# Schematic_EasyEDA_-_openELECTRO_-_ARDUIN.net
KiCad netlist of a schematic drawn in EasyEDA
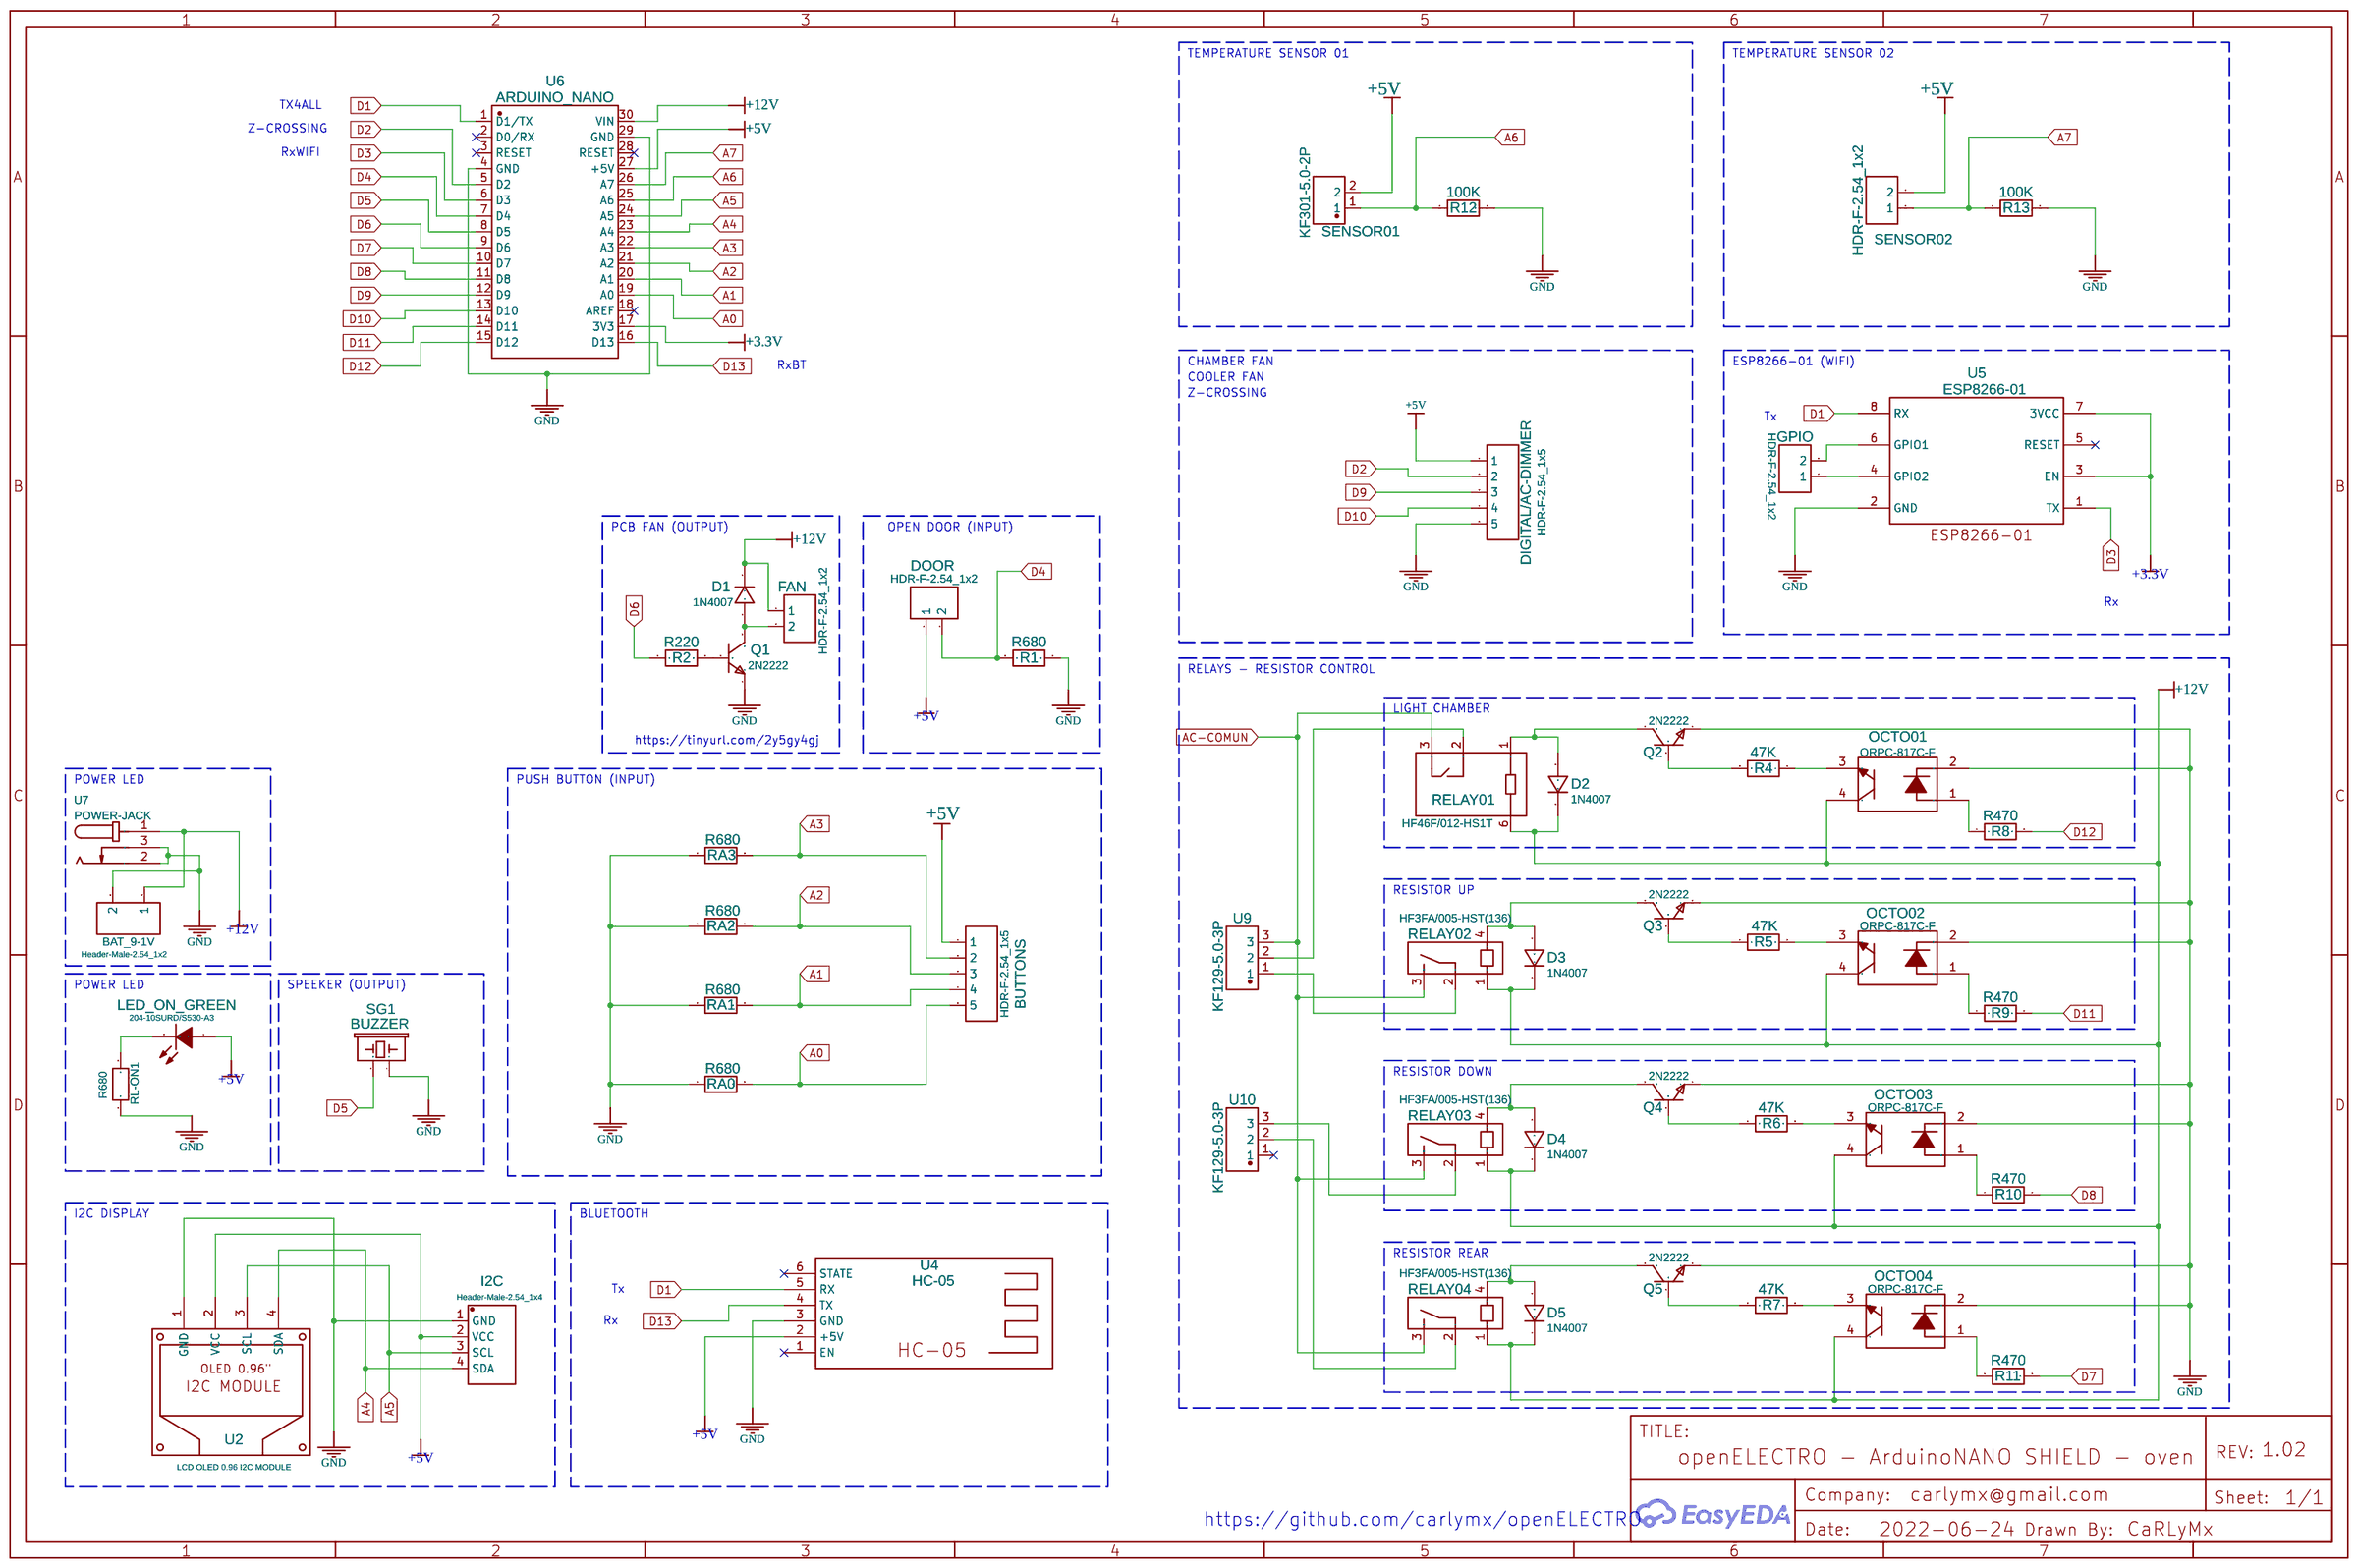
[diagram p0: schematic sheet]

(export (version "E")
  (design (tool "Eeschema 10.0.6"))
  (components
    (comp (ref "BAT_9-1V")
      (value "Header-Male-2.54_1x2")
      (fields (field (name "BOM_Manufacturer Part") "826629-2") (field (name "BOM_Supplier Part") "C86471"))
      (libsource (lib "") (part "Unknown_65_-400"))
    )
    (comp (ref "BUTTONS")
      (value "HDR-F-2.54_1x5")
      (fields (field (name "BOM_Supplier Part") "C50950"))
      (libsource (lib "") (part "HDR-F-2.54_1x5"))
    )
    (comp (ref "D1")
      (value "1N4007")
      (fields (field (name "BOM_Supplier Part") "C106903"))
      (libsource (lib "") (part "1N4007_1"))
    )
    (comp (ref "D2")
      (value "1N4007")
      (fields (field (name "BOM_Supplier Part") "C106903"))
      (libsource (lib "") (part "1N4007"))
    )
    (comp (ref "D3")
      (value "1N4007")
      (fields (field (name "BOM_Supplier Part") "C106903"))
      (libsource (lib "") (part "1N4007"))
    )
    (comp (ref "D4")
      (value "1N4007")
      (fields (field (name "BOM_Supplier Part") "C106903"))
      (libsource (lib "") (part "1N4007"))
    )
    (comp (ref "D5")
      (value "1N4007")
      (fields (field (name "BOM_Supplier Part") "C106903"))
      (libsource (lib "") (part "1N4007"))
    )
    (comp (ref "DIGITAL/AC-DIMMER")
      (value "HDR-F-2.54_1x5")
      (fields (field (name "BOM_Supplier Part") "C50950"))
      (libsource (lib "") (part "HDR-F-2.54_1x5_1"))
    )
    (comp (ref "DOOR")
      (value "HDR-F-2.54_1x2")
      (fields (field (name "BOM_Supplier Part") "C49661"))
      (libsource (lib "") (part "HDR-F-2.54_1x2"))
    )
    (comp (ref "FAN")
      (value "HDR-F-2.54_1x2")
      (fields (field (name "BOM_Supplier Part") "C49661"))
      (libsource (lib "") (part "HDR-F-2.54_1x2_2"))
    )
    (comp (ref "GPIO")
      (value "HDR-F-2.54_1x2")
      (fields (field (name "BOM_Supplier Part") "C49661"))
      (libsource (lib "") (part "HDR-F-2.54_1x2_3"))
    )
    (comp (ref "I2C")
      (value "Header-Male-2.54_1x4")
      (fields
        (field (name "BOM_Manufacturer Part") "210S-1*4P L=11.6MMGold-plated black")
        (field (name "BOM_Supplier Part") "C124378")
      )
      (libsource (lib "") (part "Unknown_290_-125"))
    )
    (comp (ref "LED_ON_GREEN")
      (value "204-10SURD/S530-A3")
      (fields (field (name "BOM_Supplier Part") "C99772"))
      (libsource (lib "") (part "Unknown_100_-315"))
    )
    (comp (ref "OCTO01")
      (value "ORPC-817C-F")
      (fields (field (name "BOM_Supplier Part") "C2842770"))
      (libsource (lib "") (part "ORPC-817C-F"))
    )
    (comp (ref "OCTO02")
      (value "ORPC-817C-F")
      (fields (field (name "BOM_Supplier Part") "C2842770"))
      (libsource (lib "") (part "ORPC-817C-F"))
    )
    (comp (ref "OCTO03")
      (value "ORPC-817C-F")
      (fields (field (name "BOM_Supplier Part") "C2842770"))
      (libsource (lib "") (part "ORPC-817C-F"))
    )
    (comp (ref "OCTO04")
      (value "ORPC-817C-F")
      (fields (field (name "BOM_Supplier Part") "C2842770"))
      (libsource (lib "") (part "ORPC-817C-F"))
    )
    (comp (ref "Q1")
      (value "2N2222")
      (fields (field (name "BOM_Supplier Part") "C118536"))
      (libsource (lib "") (part "2N2222_1"))
    )
    (comp (ref "Q2")
      (value "2N2222")
      (fields (field (name "BOM_Supplier Part") "C118536"))
      (libsource (lib "") (part "2N2222"))
    )
    (comp (ref "Q3")
      (value "2N2222")
      (fields (field (name "BOM_Supplier Part") "C118536"))
      (libsource (lib "") (part "2N2222"))
    )
    (comp (ref "Q4")
      (value "2N2222")
      (fields (field (name "BOM_Supplier Part") "C118536"))
      (libsource (lib "") (part "2N2222"))
    )
    (comp (ref "Q5")
      (value "2N2222")
      (fields (field (name "BOM_Supplier Part") "C118536"))
      (libsource (lib "") (part "2N2222"))
    )
    (comp (ref "R1") (value "R680") (libsource (lib "") (part "R_0603_EU_1")))
    (comp (ref "R2") (value "R220") (libsource (lib "") (part "R_0603_EU")))
    (comp (ref "R4") (value "47K") (libsource (lib "") (part "R_0603_EU_1")))
    (comp (ref "R5") (value "47K") (libsource (lib "") (part "R_0603_EU")))
    (comp (ref "R6") (value "47K") (libsource (lib "") (part "R_0603_EU")))
    (comp (ref "R7") (value "47K") (libsource (lib "") (part "R_0603_EU")))
    (comp (ref "R8") (value "R470") (libsource (lib "") (part "R_0603_EU")))
    (comp (ref "R9") (value "R470") (libsource (lib "") (part "R_0603_EU")))
    (comp (ref "R10") (value "R470") (libsource (lib "") (part "R_0603_EU")))
    (comp (ref "R11") (value "R470") (libsource (lib "") (part "R_0603_EU")))
    (comp (ref "R12") (value "100K") (libsource (lib "") (part "R_0603_EU")))
    (comp (ref "R13") (value "100K") (libsource (lib "") (part "R_0603_EU")))
    (comp (ref "RA0") (value "R680") (libsource (lib "") (part "Res_AXIAL-0.3(1/8W)_EU")))
    (comp (ref "RA1") (value "R680") (libsource (lib "") (part "Res_AXIAL-0.3(1/8W)_EU")))
    (comp (ref "RA2") (value "R680") (libsource (lib "") (part "Res_AXIAL-0.3(1/8W)_EU")))
    (comp (ref "RA3") (value "R680") (libsource (lib "") (part "Res_AXIAL-0.3(1/8W)_EU")))
    (comp (ref "RELAY01")
      (value "HF46F/012-HS1T")
      (fields (field (name "BOM_Supplier Part") "C2976852"))
      (libsource (lib "") (part "HF46F/012-HS1T"))
    )
    (comp (ref "RELAY02")
      (value "HF3FA/005-HST(136)")
      (fields (field (name "BOM_Supplier Part") "C712707"))
      (libsource (lib "") (part "HF3FA/005-HST(136)"))
    )
    (comp (ref "RELAY03")
      (value "HF3FA/005-HST(136)")
      (fields (field (name "BOM_Supplier Part") "C712707"))
      (libsource (lib "") (part "HF3FA/005-HST(136)"))
    )
    (comp (ref "RELAY04")
      (value "HF3FA/005-HST(136)")
      (fields (field (name "BOM_Supplier Part") "C712707"))
      (libsource (lib "") (part "HF3FA/005-HST(136)"))
    )
    (comp (ref "RL-ON1") (value "R680") (libsource (lib "") (part "Res_AXIAL-0.3(1/8W)_EU_1")))
    (comp (ref "SENSOR01")
      (value "KF301-5.0-2P")
      (fields (field (name "BOM_Supplier Part") "C474881"))
      (libsource (lib "") (part "KF301-5.0-2P"))
    )
    (comp (ref "SENSOR02")
      (value "HDR-F-2.54_1x2")
      (fields (field (name "BOM_Supplier Part") "C49661"))
      (libsource (lib "") (part "HDR-F-2.54_1x2_1"))
    )
    (comp (ref "SG1") (value "BUZZER") (libsource (lib "") (part "Unknown_225_-305")))
    (comp (ref "U2")
      (value "LCD OLED 0.96 I2C MODULE")
      (fields (field (name "BOM_Manufacturer Part") "Control Chip SSD1306"))
      (libsource (lib "") (part "Unknown_80_-135"))
    )
    (comp (ref "U4") (value "HC-05") (libsource (lib "") (part "Unknown_500_-180")))
    (comp (ref "U5") (value "ESP8266-01") (libsource (lib "") (part "ESP8266-01")))
    (comp (ref "U6")
      (value "ARDUINO_NANO")
      (fields (field (name "BOM_Supplier Part") "C9900017879"))
      (libsource (lib "") (part "ARDUINO_NANO"))
    )
    (comp (ref "U7")
      (value "POWER-JACK")
      (fields (field (name "BOM_Supplier Part") "C9900001795"))
      (libsource (lib "") (part "POWER-JACK"))
    )
    (comp (ref "U9")
      (value "KF129-5.0-3P")
      (fields (field (name "BOM_Supplier Part") "C475091"))
      (libsource (lib "") (part "KF129-5.0-3P"))
    )
    (comp (ref "U10")
      (value "KF129-5.0-3P")
      (fields (field (name "BOM_Supplier Part") "C475091"))
      (libsource (lib "") (part "KF129-5.0-3P"))
    )
  )
  (nets
    (net (code "1") (name "+3.3V") (class "Default")
      (node (ref "U5") (pin "3") (pinfunction "EN_3") (pintype "unspecified"))
      (node (ref "U5") (pin "7") (pinfunction "3VCC_7") (pintype "unspecified"))
      (node (ref "U6") (pin "17") (pinfunction "3V3_17") (pintype "unspecified"))
    )
    (net (code "2") (name "+5V") (class "Default")
      (node (ref "BUTTONS") (pin "1") (pinfunction "1_1") (pintype "unspecified"))
      (node (ref "DIGITAL/AC-DIMMER") (pin "1") (pinfunction "1_1") (pintype "unspecified"))
      (node (ref "DOOR") (pin "1") (pinfunction "1_1") (pintype "input"))
      (node (ref "I2C") (pin "2") (pinfunction "VCC_2") (pintype "unspecified"))
      (node (ref "LED_ON_GREEN") (pin "1") (pinfunction "A_1") (pintype "unspecified"))
      (node (ref "SENSOR01") (pin "2") (pinfunction "2_2") (pintype "unspecified"))
      (node (ref "SENSOR02") (pin "2") (pinfunction "2_2") (pintype "input"))
      (node (ref "U2") (pin "2") (pinfunction "VCC_2") (pintype "unspecified"))
      (node (ref "U4") (pin "2") (pinfunction "+5V_2") (pintype "unspecified"))
      (node (ref "U6") (pin "27") (pinfunction "+5V_27") (pintype "unspecified"))
    )
    (net (code "3") (name "+12V") (class "Default")
      (node (ref "BAT_9-1V") (pin "1") (pinfunction "1_1") (pintype "unspecified"))
      (node (ref "D1") (pin "1") (pinfunction "1_1") (pintype "unspecified"))
      (node (ref "D2") (pin "1") (pinfunction "1_1") (pintype "unspecified"))
      (node (ref "D3") (pin "1") (pinfunction "1_1") (pintype "unspecified"))
      (node (ref "D4") (pin "1") (pinfunction "1_1") (pintype "unspecified"))
      (node (ref "D5") (pin "1") (pinfunction "1_1") (pintype "unspecified"))
      (node (ref "FAN") (pin "1") (pinfunction "1_1") (pintype "input"))
      (node (ref "OCTO01") (pin "4") (pinfunction "4_4") (pintype "unspecified"))
      (node (ref "OCTO02") (pin "4") (pinfunction "4_4") (pintype "unspecified"))
      (node (ref "OCTO03") (pin "4") (pinfunction "4_4") (pintype "unspecified"))
      (node (ref "OCTO04") (pin "4") (pinfunction "4_4") (pintype "unspecified"))
      (node (ref "RELAY01") (pin "6") (pinfunction "6_6") (pintype "unspecified"))
      (node (ref "RELAY02") (pin "1") (pinfunction "1_1") (pintype "unspecified"))
      (node (ref "RELAY03") (pin "1") (pinfunction "1_1") (pintype "unspecified"))
      (node (ref "RELAY04") (pin "1") (pinfunction "1_1") (pintype "unspecified"))
      (node (ref "U6") (pin "30") (pinfunction "VIN_30") (pintype "unspecified"))
      (node (ref "U7") (pin "1") (pinfunction "1_1") (pintype "unspecified"))
    )
    (net (code "4") (name "A0") (class "Default")
      (node (ref "BUTTONS") (pin "5") (pinfunction "5_5") (pintype "unspecified"))
      (node (ref "RA0") (pin "2") (pinfunction "2_2") (pintype "unspecified"))
      (node (ref "U6") (pin "19") (pinfunction "A0_19") (pintype "unspecified"))
    )
    (net (code "5") (name "A1") (class "Default")
      (node (ref "BUTTONS") (pin "4") (pinfunction "4_4") (pintype "unspecified"))
      (node (ref "RA1") (pin "2") (pinfunction "2_2") (pintype "unspecified"))
      (node (ref "U6") (pin "20") (pinfunction "A1_20") (pintype "unspecified"))
    )
    (net (code "6") (name "A2") (class "Default")
      (node (ref "BUTTONS") (pin "3") (pinfunction "3_3") (pintype "unspecified"))
      (node (ref "RA2") (pin "2") (pinfunction "2_2") (pintype "unspecified"))
      (node (ref "U6") (pin "21") (pinfunction "A2_21") (pintype "unspecified"))
    )
    (net (code "7") (name "A3") (class "Default")
      (node (ref "BUTTONS") (pin "2") (pinfunction "2_2") (pintype "unspecified"))
      (node (ref "RA3") (pin "2") (pinfunction "2_2") (pintype "unspecified"))
      (node (ref "U6") (pin "22") (pinfunction "A3_22") (pintype "unspecified"))
    )
    (net (code "8") (name "A4") (class "Default")
      (node (ref "I2C") (pin "4") (pinfunction "SDA_4") (pintype "unspecified"))
      (node (ref "U2") (pin "4") (pinfunction "SDA_4") (pintype "unspecified"))
      (node (ref "U6") (pin "23") (pinfunction "A4_23") (pintype "unspecified"))
    )
    (net (code "9") (name "A5") (class "Default")
      (node (ref "I2C") (pin "3") (pinfunction "SCL_3") (pintype "unspecified"))
      (node (ref "U2") (pin "3") (pinfunction "SCL_3") (pintype "unspecified"))
      (node (ref "U6") (pin "24") (pinfunction "A5_24") (pintype "unspecified"))
    )
    (net (code "10") (name "A6") (class "Default")
      (node (ref "R12") (pin "1") (pinfunction "1_1") (pintype "unspecified"))
      (node (ref "SENSOR01") (pin "1") (pinfunction "1_1") (pintype "unspecified"))
      (node (ref "U6") (pin "25") (pinfunction "A6_25") (pintype "unspecified"))
    )
    (net (code "11") (name "A7") (class "Default")
      (node (ref "R13") (pin "1") (pinfunction "1_1") (pintype "unspecified"))
      (node (ref "SENSOR02") (pin "1") (pinfunction "1_1") (pintype "input"))
      (node (ref "U6") (pin "26") (pinfunction "A7_26") (pintype "unspecified"))
    )
    (net (code "12") (name "AC-COMUN") (class "Default")
      (node (ref "RELAY01") (pin "3") (pinfunction "3_3") (pintype "unspecified"))
      (node (ref "RELAY02") (pin "3") (pinfunction "3_3") (pintype "unspecified"))
      (node (ref "RELAY03") (pin "3") (pinfunction "3_3") (pintype "unspecified"))
      (node (ref "RELAY04") (pin "3") (pinfunction "3_3") (pintype "unspecified"))
      (node (ref "U9") (pin "3") (pinfunction "3_3") (pintype "unspecified"))
    )
    (net (code "13") (name "D1") (class "Default")
      (node (ref "U4") (pin "5") (pinfunction "RX_5") (pintype "unspecified"))
      (node (ref "U5") (pin "8") (pinfunction "RX_8") (pintype "unspecified"))
      (node (ref "U6") (pin "1") (pinfunction "D1/TX_1") (pintype "unspecified"))
    )
    (net (code "14") (name "D2") (class "Default")
      (node (ref "DIGITAL/AC-DIMMER") (pin "2") (pinfunction "2_2") (pintype "unspecified"))
      (node (ref "U6") (pin "5") (pinfunction "D2_5") (pintype "unspecified"))
    )
    (net (code "15") (name "D3") (class "Default")
      (node (ref "U5") (pin "1") (pinfunction "TX_1") (pintype "unspecified"))
      (node (ref "U6") (pin "6") (pinfunction "D3_6") (pintype "unspecified"))
    )
    (net (code "16") (name "D4") (class "Default")
      (node (ref "DOOR") (pin "2") (pinfunction "2_2") (pintype "input"))
      (node (ref "R1") (pin "2") (pinfunction "2_2") (pintype "unspecified"))
      (node (ref "U6") (pin "7") (pinfunction "D4_7") (pintype "unspecified"))
    )
    (net (code "17") (name "D5") (class "Default")
      (node (ref "SG1") (pin "+") (pinfunction "1_+") (pintype "unspecified"))
      (node (ref "U6") (pin "8") (pinfunction "D5_8") (pintype "unspecified"))
    )
    (net (code "18") (name "D6") (class "Default")
      (node (ref "R2") (pin "1") (pinfunction "1_1") (pintype "unspecified"))
      (node (ref "U6") (pin "9") (pinfunction "D6_9") (pintype "unspecified"))
    )
    (net (code "19") (name "D7") (class "Default")
      (node (ref "R11") (pin "2") (pinfunction "2_2") (pintype "unspecified"))
      (node (ref "U6") (pin "10") (pinfunction "D7_10") (pintype "unspecified"))
    )
    (net (code "20") (name "D8") (class "Default")
      (node (ref "R10") (pin "2") (pinfunction "2_2") (pintype "unspecified"))
      (node (ref "U6") (pin "11") (pinfunction "D8_11") (pintype "unspecified"))
    )
    (net (code "21") (name "D9") (class "Default")
      (node (ref "DIGITAL/AC-DIMMER") (pin "3") (pinfunction "3_3") (pintype "unspecified"))
      (node (ref "U6") (pin "12") (pinfunction "D9_12") (pintype "unspecified"))
    )
    (net (code "22") (name "D10") (class "Default")
      (node (ref "DIGITAL/AC-DIMMER") (pin "4") (pinfunction "4_4") (pintype "unspecified"))
      (node (ref "U6") (pin "13") (pinfunction "D10_13") (pintype "unspecified"))
    )
    (net (code "23") (name "D11") (class "Default")
      (node (ref "R9") (pin "2") (pinfunction "2_2") (pintype "unspecified"))
      (node (ref "U6") (pin "14") (pinfunction "D11_14") (pintype "unspecified"))
    )
    (net (code "24") (name "D12") (class "Default")
      (node (ref "R8") (pin "2") (pinfunction "2_2") (pintype "unspecified"))
      (node (ref "U6") (pin "15") (pinfunction "D12_15") (pintype "unspecified"))
    )
    (net (code "25") (name "D13") (class "Default")
      (node (ref "U4") (pin "4") (pinfunction "TX_4") (pintype "unspecified"))
      (node (ref "U6") (pin "16") (pinfunction "D13_16") (pintype "unspecified"))
    )
    (net (code "26") (name "GND") (class "Default")
      (node (ref "BAT_9-1V") (pin "2") (pinfunction "2_2") (pintype "unspecified"))
      (node (ref "DIGITAL/AC-DIMMER") (pin "5") (pinfunction "5_5") (pintype "unspecified"))
      (node (ref "I2C") (pin "1") (pinfunction "GND_1") (pintype "unspecified"))
      (node (ref "OCTO01") (pin "2") (pinfunction "2_2") (pintype "unspecified"))
      (node (ref "OCTO02") (pin "2") (pinfunction "2_2") (pintype "unspecified"))
      (node (ref "OCTO03") (pin "2") (pinfunction "2_2") (pintype "unspecified"))
      (node (ref "OCTO04") (pin "2") (pinfunction "2_2") (pintype "unspecified"))
      (node (ref "Q1") (pin "1") (pinfunction "E_1") (pintype "unspecified"))
      (node (ref "Q2") (pin "1") (pinfunction "E_1") (pintype "unspecified"))
      (node (ref "Q3") (pin "1") (pinfunction "E_1") (pintype "unspecified"))
      (node (ref "Q4") (pin "1") (pinfunction "E_1") (pintype "unspecified"))
      (node (ref "Q5") (pin "1") (pinfunction "E_1") (pintype "unspecified"))
      (node (ref "R1") (pin "1") (pinfunction "1_1") (pintype "unspecified"))
      (node (ref "R12") (pin "2") (pinfunction "2_2") (pintype "unspecified"))
      (node (ref "R13") (pin "2") (pinfunction "2_2") (pintype "unspecified"))
      (node (ref "RA0") (pin "1") (pinfunction "1_1") (pintype "unspecified"))
      (node (ref "RA1") (pin "1") (pinfunction "1_1") (pintype "unspecified"))
      (node (ref "RA2") (pin "1") (pinfunction "1_1") (pintype "unspecified"))
      (node (ref "RA3") (pin "1") (pinfunction "1_1") (pintype "unspecified"))
      (node (ref "RL-ON1") (pin "1") (pinfunction "1_1") (pintype "unspecified"))
      (node (ref "SG1") (pin "-") (pinfunction "2_-") (pintype "unspecified"))
      (node (ref "U2") (pin "1") (pinfunction "GND_1") (pintype "unspecified"))
      (node (ref "U4") (pin "3") (pinfunction "GND_3") (pintype "unspecified"))
      (node (ref "U5") (pin "2") (pinfunction "GND_2") (pintype "unspecified"))
      (node (ref "U6") (pin "29") (pinfunction "GND_29") (pintype "unspecified"))
      (node (ref "U6") (pin "4") (pinfunction "GND_4") (pintype "unspecified"))
      (node (ref "U7") (pin "2") (pinfunction "2_2") (pintype "unspecified"))
      (node (ref "U7") (pin "3") (pinfunction "3_3") (pintype "unspecified"))
    )
    (net (code "27") (name "Net-(LED_ON_GREEN-K)") (class "Default")
      (node (ref "LED_ON_GREEN") (pin "2") (pinfunction "K_2") (pintype "unspecified"))
      (node (ref "RL-ON1") (pin "2") (pinfunction "2_2") (pintype "unspecified"))
    )
    (net (code "28") (name "Net-(OCTO01-Pad1)") (class "Default")
      (node (ref "OCTO01") (pin "1") (pinfunction "1_1") (pintype "unspecified"))
      (node (ref "R8") (pin "1") (pinfunction "1_1") (pintype "unspecified"))
    )
    (net (code "29") (name "Net-(OCTO01-Pad3)") (class "Default")
      (node (ref "OCTO01") (pin "3") (pinfunction "3_3") (pintype "unspecified"))
      (node (ref "R4") (pin "1") (pinfunction "1_1") (pintype "unspecified"))
    )
    (net (code "30") (name "Net-(OCTO02-Pad1)") (class "Default")
      (node (ref "OCTO02") (pin "1") (pinfunction "1_1") (pintype "unspecified"))
      (node (ref "R9") (pin "1") (pinfunction "1_1") (pintype "unspecified"))
    )
    (net (code "31") (name "Net-(OCTO02-Pad3)") (class "Default")
      (node (ref "OCTO02") (pin "3") (pinfunction "3_3") (pintype "unspecified"))
      (node (ref "R5") (pin "2") (pinfunction "2_2") (pintype "unspecified"))
    )
    (net (code "32") (name "Net-(OCTO03-Pad1)") (class "Default")
      (node (ref "OCTO03") (pin "1") (pinfunction "1_1") (pintype "unspecified"))
      (node (ref "R10") (pin "1") (pinfunction "1_1") (pintype "unspecified"))
    )
    (net (code "33") (name "Net-(OCTO03-Pad3)") (class "Default")
      (node (ref "OCTO03") (pin "3") (pinfunction "3_3") (pintype "unspecified"))
      (node (ref "R6") (pin "2") (pinfunction "2_2") (pintype "unspecified"))
    )
    (net (code "34") (name "Net-(OCTO04-Pad1)") (class "Default")
      (node (ref "OCTO04") (pin "1") (pinfunction "1_1") (pintype "unspecified"))
      (node (ref "R11") (pin "1") (pinfunction "1_1") (pintype "unspecified"))
    )
    (net (code "35") (name "Net-(OCTO04-Pad3)") (class "Default")
      (node (ref "OCTO04") (pin "3") (pinfunction "3_3") (pintype "unspecified"))
      (node (ref "R7") (pin "2") (pinfunction "2_2") (pintype "unspecified"))
    )
    (net (code "36") (name "Net-(Q1-B)") (class "Default")
      (node (ref "Q1") (pin "2") (pinfunction "B_2") (pintype "unspecified"))
      (node (ref "R2") (pin "2") (pinfunction "2_2") (pintype "unspecified"))
    )
    (net (code "37") (name "Net-(Q1-C)") (class "Default")
      (node (ref "D1") (pin "2") (pinfunction "2_2") (pintype "unspecified"))
      (node (ref "FAN") (pin "2") (pinfunction "2_2") (pintype "input"))
      (node (ref "Q1") (pin "3") (pinfunction "C_3") (pintype "unspecified"))
    )
    (net (code "38") (name "Net-(Q2-B)") (class "Default")
      (node (ref "Q2") (pin "2") (pinfunction "B_2") (pintype "unspecified"))
      (node (ref "R4") (pin "2") (pinfunction "2_2") (pintype "unspecified"))
    )
    (net (code "39") (name "Net-(Q2-C)") (class "Default")
      (node (ref "D2") (pin "2") (pinfunction "2_2") (pintype "unspecified"))
      (node (ref "Q2") (pin "3") (pinfunction "C_3") (pintype "unspecified"))
      (node (ref "RELAY01") (pin "1") (pinfunction "1_1") (pintype "unspecified"))
    )
    (net (code "40") (name "Net-(Q3-B)") (class "Default")
      (node (ref "Q3") (pin "2") (pinfunction "B_2") (pintype "unspecified"))
      (node (ref "R5") (pin "1") (pinfunction "1_1") (pintype "unspecified"))
    )
    (net (code "41") (name "Net-(Q3-C)") (class "Default")
      (node (ref "D3") (pin "2") (pinfunction "2_2") (pintype "unspecified"))
      (node (ref "Q3") (pin "3") (pinfunction "C_3") (pintype "unspecified"))
      (node (ref "RELAY02") (pin "4") (pinfunction "4_4") (pintype "unspecified"))
    )
    (net (code "42") (name "Net-(Q4-B)") (class "Default")
      (node (ref "Q4") (pin "2") (pinfunction "B_2") (pintype "unspecified"))
      (node (ref "R6") (pin "1") (pinfunction "1_1") (pintype "unspecified"))
    )
    (net (code "43") (name "Net-(Q4-C)") (class "Default")
      (node (ref "D4") (pin "2") (pinfunction "2_2") (pintype "unspecified"))
      (node (ref "Q4") (pin "3") (pinfunction "C_3") (pintype "unspecified"))
      (node (ref "RELAY03") (pin "4") (pinfunction "4_4") (pintype "unspecified"))
    )
    (net (code "44") (name "Net-(Q5-B)") (class "Default")
      (node (ref "Q5") (pin "2") (pinfunction "B_2") (pintype "unspecified"))
      (node (ref "R7") (pin "1") (pinfunction "1_1") (pintype "unspecified"))
    )
    (net (code "45") (name "Net-(Q5-C)") (class "Default")
      (node (ref "D5") (pin "2") (pinfunction "2_2") (pintype "unspecified"))
      (node (ref "Q5") (pin "3") (pinfunction "C_3") (pintype "unspecified"))
      (node (ref "RELAY04") (pin "4") (pinfunction "4_4") (pintype "unspecified"))
    )
    (net (code "46") (name "Net-(RELAY01-Pad2)") (class "Default")
      (node (ref "RELAY01") (pin "2") (pinfunction "2_2") (pintype "unspecified"))
      (node (ref "U9") (pin "2") (pinfunction "2_2") (pintype "unspecified"))
    )
    (net (code "47") (name "Net-(RELAY02-Pad2)") (class "Default")
      (node (ref "RELAY02") (pin "2") (pinfunction "2_2") (pintype "unspecified"))
      (node (ref "U9") (pin "1") (pinfunction "1_1") (pintype "unspecified"))
    )
    (net (code "48") (name "Net-(RELAY03-Pad2)") (class "Default")
      (node (ref "RELAY03") (pin "2") (pinfunction "2_2") (pintype "unspecified"))
      (node (ref "U10") (pin "3") (pinfunction "3_3") (pintype "unspecified"))
    )
    (net (code "49") (name "Net-(RELAY04-Pad2)") (class "Default")
      (node (ref "RELAY04") (pin "2") (pinfunction "2_2") (pintype "unspecified"))
      (node (ref "U10") (pin "2") (pinfunction "2_2") (pintype "unspecified"))
    )
    (net (code "50") (name "Net-(U5-GPIO1)") (class "Default")
      (node (ref "GPIO") (pin "2") (pinfunction "2_2") (pintype "input"))
      (node (ref "U5") (pin "6") (pinfunction "GPIO1_6") (pintype "unspecified"))
    )
    (net (code "51") (name "Net-(U5-GPIO2)") (class "Default")
      (node (ref "GPIO") (pin "1") (pinfunction "1_1") (pintype "input"))
      (node (ref "U5") (pin "4") (pinfunction "GPIO2_4") (pintype "unspecified"))
    )
    (net (code "52") (name "unconnected-(U4-EN-Pad1)") (class "Default")
      (node (ref "U4") (pin "1") (pinfunction "EN_1") (pintype "unspecified+no_connect"))
    )
    (net (code "53") (name "unconnected-(U4-STATE-Pad6)") (class "Default")
      (node (ref "U4") (pin "6") (pinfunction "STATE_6") (pintype "unspecified+no_connect"))
    )
    (net (code "54") (name "unconnected-(U5-RESET-Pad5)") (class "Default")
      (node (ref "U5") (pin "5") (pinfunction "RESET_5") (pintype "unspecified+no_connect"))
    )
    (net (code "55") (name "unconnected-(U6-AREF-Pad18)") (class "Default")
      (node (ref "U6") (pin "18") (pinfunction "AREF_18") (pintype "unspecified+no_connect"))
    )
    (net (code "56") (name "unconnected-(U6-D0{slash}RX-Pad2)") (class "Default")
      (node (ref "U6") (pin "2") (pinfunction "D0/RX_2") (pintype "unspecified+no_connect"))
    )
    (net (code "57") (name "unconnected-(U6-RESET-Pad3)") (class "Default")
      (node (ref "U6") (pin "3") (pinfunction "RESET_3") (pintype "unspecified+no_connect"))
    )
    (net (code "58") (name "unconnected-(U6-RESET-Pad28)") (class "Default")
      (node (ref "U6") (pin "28") (pinfunction "RESET_28") (pintype "unspecified+no_connect"))
    )
    (net (code "59") (name "unconnected-(U10-Pad1)") (class "Default")
      (node (ref "U10") (pin "1") (pinfunction "1_1") (pintype "unspecified+no_connect"))
    )
  )
)
